# Sound.net
KiCad netlist of a schematic drawn in Altium Designer
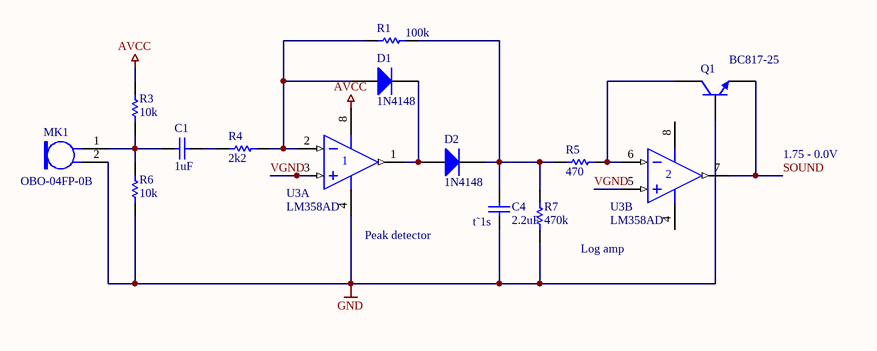
[diagram p0: Sound.SchDoc]

(export (version "E")
  (design (tool "Eeschema 10.0.6"))
  (components
    (comp (ref "C1")
      (value "1uF")
      (footprint "CAPC0805(2012)145_M")
      (description "CAP 1uF 10V ±20% 0805 (2012 Metric) Thickness 1.45mm SMD")
      (fields (field (name "TOLERANCE") "±20%") (field (name "Comment") "CAP 1uF 10V 0805(2012)"))
      (libsource (lib "Altium Content Vault") (part "CMP-1036-04740-1"))
    )
    (comp (ref "C4")
      (value "2.2uF")
      (footprint "CAPC0805(2012)145_N")
      (description "CAP 2.2uF 10V ±10% 0805 (2012 Metric) Thickness 1.45mm SMD")
      (fields (field (name "TOLERANCE") "±10%") (field (name "Comment") "CAP 2.2uF 10V 0805(2012)"))
      (libsource (lib "Altium Content Vault") (part "CMP-1036-04824-1"))
    )
    (comp (ref "D1")
      (value "1N4148")
      (footprint "SOD-323F")
      (description "High Conductance Fast Diode")
      (fields (field (name "PUBLISHER") "Altium Limited"))
      (libsource (lib "FSC Discrete Diode") (part "1N4148"))
    )
    (comp (ref "D2")
      (value "1N4148")
      (footprint "SOD-323F")
      (description "High Conductance Fast Diode")
      (fields (field (name "PUBLISHER") "Altium Limited"))
      (libsource (lib "FSC Discrete Diode") (part "1N4148"))
    )
    (comp (ref "MK1")
      (value "OBO-04FP-0B")
      (footprint "OBO-04FP-0B")
      (description "Microphone")
      (fields (field (name "PUBLISHER") "Altium Limited"))
      (libsource (lib "Miscellaneous Devices") (part "Mic2"))
    )
    (comp (ref "Q1")
      (value "BC817-25")
      (footprint "SOT23_N")
      (description "NPN General Purpose Amplifier")
      (fields (field (name "PUBLISHER") "Altium Limited"))
      (libsource (lib "FSC Discrete BJT") (part "BC817-25"))
    )
    (comp (ref "R1")
      (value "100k")
      (footprint "6-0805")
      (fields (field (name "PUBLISHER") "Altium Limited"))
      (libsource (lib "Panasonic Resistor") (part "ERJ6RB"))
    )
    (comp (ref "R3")
      (value "10k")
      (footprint "6-0805")
      (fields (field (name "PUBLISHER") "Altium Limited"))
      (libsource (lib "Panasonic Resistor") (part "ERJ6RB"))
    )
    (comp (ref "R4")
      (value "2k2")
      (footprint "6-0805")
      (fields (field (name "PUBLISHER") "Altium Limited"))
      (libsource (lib "Panasonic Resistor") (part "ERJ6RB"))
    )
    (comp (ref "R5")
      (value "470")
      (footprint "6-0805")
      (fields (field (name "PUBLISHER") "Altium Limited"))
      (libsource (lib "Panasonic Resistor") (part "ERJ6RB"))
    )
    (comp (ref "R6")
      (value "10k")
      (footprint "6-0805")
      (fields (field (name "PUBLISHER") "Altium Limited"))
      (libsource (lib "Panasonic Resistor") (part "ERJ6RB"))
    )
    (comp (ref "R7")
      (value "470k")
      (footprint "6-0805")
      (fields (field (name "PUBLISHER") "Altium Limited"))
      (libsource (lib "Panasonic Resistor") (part "ERJ6RB"))
    )
    (comp (ref "U3")
      (value "LM358AD")
      (footprint "SOIC127P600X175-8AN")
      (description "Dual Operational Amplifier")
      (fields (field (name "PUBLISHER") "Altium Limited"))
      (libsource (lib "TI Operational Amplifier") (part "LM358AD"))
    )
  )
  (nets
    (net (code "1") (name "/SOUND") (class "Default")
      (node (ref "Q1") (pin "2") (pinfunction "E_2") (pintype "passive"))
      (node (ref "U3") (pin "7") (pinfunction "OUT_7") (pintype "output"))
    )
    (net (code "2") (name "/VGND") (class "Default")
      (node (ref "U3") (pin "3") (pinfunction "IN+_3") (pintype "input"))
      (node (ref "U3") (pin "5") (pinfunction "IN+_5") (pintype "input"))
    )
    (net (code "3") (name "AVCC") (class "Default")
      (node (ref "R3") (pin "2") (pinfunction "2_2") (pintype "passive"))
      (node (ref "U3") (pin "8") (pinfunction "V+_8") (pintype "power_in"))
    )
    (net (code "4") (name "GND") (class "Default")
      (node (ref "C4") (pin "1") (pinfunction "1_1") (pintype "passive"))
      (node (ref "MK1") (pin "2") (pinfunction "2_2") (pintype "passive"))
      (node (ref "Q1") (pin "1") (pinfunction "B_1") (pintype "passive"))
      (node (ref "R6") (pin "1") (pinfunction "1_1") (pintype "passive"))
      (node (ref "R7") (pin "2") (pinfunction "2_2") (pintype "passive"))
      (node (ref "U3") (pin "4") (pinfunction "V-_4") (pintype "power_in"))
    )
    (net (code "5") (name "Net-(C1-Pad1)") (class "Default")
      (node (ref "C1") (pin "1") (pinfunction "1_1") (pintype "passive"))
      (node (ref "R4") (pin "2") (pinfunction "2_2") (pintype "passive"))
    )
    (net (code "6") (name "Net-(C1-Pad2)") (class "Default")
      (node (ref "C1") (pin "2") (pinfunction "2_2") (pintype "passive"))
      (node (ref "MK1") (pin "1") (pinfunction "1_1") (pintype "passive"))
      (node (ref "R3") (pin "1") (pinfunction "1_1") (pintype "passive"))
      (node (ref "R6") (pin "2") (pinfunction "2_2") (pintype "passive"))
    )
    (net (code "7") (name "Net-(D1-A)") (class "Default")
      (node (ref "D1") (pin "1") (pinfunction "A_1") (pintype "passive"))
      (node (ref "R1") (pin "2") (pinfunction "2_2") (pintype "passive"))
      (node (ref "R4") (pin "1") (pinfunction "1_1") (pintype "passive"))
      (node (ref "U3") (pin "2") (pinfunction "IN-_2") (pintype "input"))
    )
    (net (code "8") (name "Net-(D1-K)") (class "Default")
      (node (ref "D1") (pin "2") (pinfunction "K_2") (pintype "passive"))
      (node (ref "D2") (pin "1") (pinfunction "A_1") (pintype "passive"))
      (node (ref "U3") (pin "1") (pinfunction "OUT_1") (pintype "output"))
    )
    (net (code "9") (name "Net-(D2-K)") (class "Default")
      (node (ref "C4") (pin "2") (pinfunction "2_2") (pintype "passive"))
      (node (ref "D2") (pin "2") (pinfunction "K_2") (pintype "passive"))
      (node (ref "R1") (pin "1") (pinfunction "1_1") (pintype "passive"))
      (node (ref "R5") (pin "1") (pinfunction "1_1") (pintype "passive"))
      (node (ref "R7") (pin "1") (pinfunction "1_1") (pintype "passive"))
    )
    (net (code "10") (name "Net-(Q1-C)") (class "Default")
      (node (ref "Q1") (pin "3") (pinfunction "C_3") (pintype "passive"))
      (node (ref "R5") (pin "2") (pinfunction "2_2") (pintype "passive"))
      (node (ref "U3") (pin "6") (pinfunction "IN-_6") (pintype "input"))
    )
    (net (code "11") (name "unconnected-(U3B-V+-Pad8)") (class "Default")
      (node (ref "U3") (pin "8") (pinfunction "V+_8") (pintype "power_in"))
    )
    (net (code "12") (name "unconnected-(U3B-V--Pad4)") (class "Default")
      (node (ref "U3") (pin "4") (pinfunction "V-_4") (pintype "power_in"))
    )
  )
)
